# MCU.net
KiCad netlist of a schematic drawn in Altium Designer
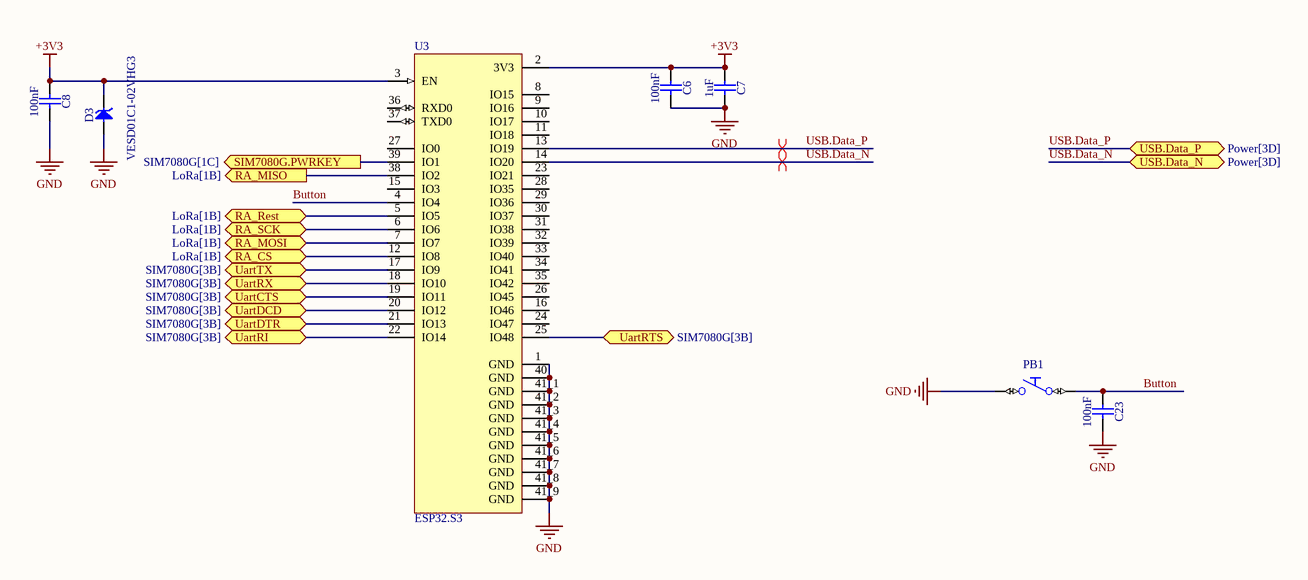
[diagram p0: MCU.SchDoc]

(export (version "E")
  (design (tool "Eeschema 10.0.6"))
  (components
    (comp (ref "C6")
      (value "100nF")
      (footprint "CAPC1608X90N")
      (description "Non-polarised capacitor")
      (fields
        (field (name "PART NUMBER") "CC0603_100NF_25V_20%_X5R_TDK_CGA3E2X5R1E104M080")
        (field (name "VOLTAGE") "25V")
        (field (name "AUTHOR") "CERN DEM BC")
      )
      (libsource (lib "Capacitors") (part "Capacitor - non polarized"))
    )
    (comp (ref "C7")
      (value "1uF")
      (footprint "CAPC1608X90N")
      (description "Non-polarised capacitor")
      (fields
        (field (name "PART NUMBER") "CC0603_1UF_10V_10%_X5R")
        (field (name "VOLTAGE") "10V")
        (field (name "AUTHOR") "CERN DEM HF")
      )
      (libsource (lib "Capacitors") (part "Capacitor - non polarized"))
    )
    (comp (ref "C8")
      (value "100nF")
      (footprint "CAPC1608X90N")
      (description "Non-polarised capacitor")
      (fields
        (field (name "PART NUMBER") "CC0603_100NF_25V_20%_X5R_TDK_CGA3E2X5R1E104M080")
        (field (name "VOLTAGE") "25V")
        (field (name "AUTHOR") "CERN DEM BC")
      )
      (libsource (lib "Capacitors") (part "Capacitor - non polarized"))
    )
    (comp (ref "C23")
      (value "100nF")
      (footprint "CAPC1608X90N")
      (description "Non-polarised capacitor")
      (fields
        (field (name "PART NUMBER") "CC0603_100NF_25V_20%_X5R_TDK_CGA3E2X5R1E104M080")
        (field (name "VOLTAGE") "25V")
        (field (name "AUTHOR") "CERN DEM BC")
      )
      (libsource (lib "Capacitors") (part "Capacitor - non polarized"))
    )
    (comp (ref "D3")
      (value "VESD01C1-02VHG3")
      (footprint "SODFL1608X70N")
      (description "Transient Voltage Suppressor Diode (Uni-Directional)")
      (fields
        (field (name "VOLTAGE") "1V")
        (field (name "POWER") "100W")
        (field (name "AUTHOR") "CERN DEM BC")
      )
      (libsource (lib "ICs And Semiconductors") (part "Diode TVS Uni-Directional"))
    )
    (comp (ref "PB1")
      (value "Push Button")
      (footprint "PB_C&K_KSS221GLFS")
      (description "Push-Button Switch SPST")
      (fields
        (field (name "PART NUMBER") "PB_C&K_KSS221GLFS")
        (field (name "MANUFACTURER") "C&K")
        (field (name "AUTHOR") "CERN DEM BC")
      )
      (libsource (lib "Eletro-mechanical") (part "PB SPST 1C-2NO"))
    )
    (comp (ref "U3")
      (value "ESP32.S3")
      (footprint "IC.ESP32.S3.WROOM.1U")
      (libsource (lib "ParsaAltiumSCHLIB") (part "IC.ESP32.S3.WROOM.1U"))
    )
  )
  (nets
    (net (code "1") (name "+3V3") (class "Default")
      (node (ref "C6") (pin "1") (pinfunction "1_1") (pintype "passive"))
      (node (ref "C7") (pin "1") (pinfunction "1_1") (pintype "passive"))
      (node (ref "C8") (pin "1") (pinfunction "1_1") (pintype "passive"))
      (node (ref "D3") (pin "1") (pinfunction "C_1") (pintype "passive"))
      (node (ref "U3") (pin "2") (pinfunction "3V3_2") (pintype "power_in"))
      (node (ref "U3") (pin "3") (pinfunction "EN_3") (pintype "input"))
    )
    (net (code "2") (name "/Button") (class "Default")
      (node (ref "C23") (pin "1") (pinfunction "1_1") (pintype "passive"))
      (node (ref "PB1") (pin "1") (pinfunction "C_1") (pintype "bidirectional"))
      (node (ref "U3") (pin "4") (pinfunction "IO4_4") (pintype "passive"))
    )
    (net (code "3") (name "/RA_CS") (class "Default")
      (node (ref "U3") (pin "12") (pinfunction "IO8_12") (pintype "passive"))
    )
    (net (code "4") (name "/RA_MISO") (class "Default")
      (node (ref "U3") (pin "38") (pinfunction "IO2_38") (pintype "passive"))
    )
    (net (code "5") (name "/RA_MOSI") (class "Default")
      (node (ref "U3") (pin "7") (pinfunction "IO7_7") (pintype "passive"))
    )
    (net (code "6") (name "/RA_Rest") (class "Default")
      (node (ref "U3") (pin "5") (pinfunction "IO5_5") (pintype "passive"))
    )
    (net (code "7") (name "/RA_SCK") (class "Default")
      (node (ref "U3") (pin "6") (pinfunction "IO6_6") (pintype "passive"))
    )
    (net (code "8") (name "/SIM7080G.PWRKEY") (class "Default")
      (node (ref "U3") (pin "39") (pinfunction "IO1_39") (pintype "passive"))
    )
    (net (code "9") (name "/USB.Data_N") (class "Default")
      (node (ref "U3") (pin "14") (pinfunction "IO20_14") (pintype "passive"))
    )
    (net (code "10") (name "/USB.Data_P") (class "Default")
      (node (ref "U3") (pin "13") (pinfunction "IO19_13") (pintype "passive"))
    )
    (net (code "11") (name "/UartCTS") (class "Default")
      (node (ref "U3") (pin "19") (pinfunction "IO11_19") (pintype "passive"))
    )
    (net (code "12") (name "/UartDCD") (class "Default")
      (node (ref "U3") (pin "20") (pinfunction "IO12_20") (pintype "passive"))
    )
    (net (code "13") (name "/UartDTR") (class "Default")
      (node (ref "U3") (pin "21") (pinfunction "IO13_21") (pintype "passive"))
    )
    (net (code "14") (name "/UartRI") (class "Default")
      (node (ref "U3") (pin "22") (pinfunction "IO14_22") (pintype "passive"))
    )
    (net (code "15") (name "/UartRTS") (class "Default")
      (node (ref "U3") (pin "25") (pinfunction "IO48_25") (pintype "passive"))
    )
    (net (code "16") (name "/UartRX") (class "Default")
      (node (ref "U3") (pin "18") (pinfunction "IO10_18") (pintype "passive"))
    )
    (net (code "17") (name "/UartTX") (class "Default")
      (node (ref "U3") (pin "17") (pinfunction "IO9_17") (pintype "passive"))
    )
    (net (code "18") (name "GND") (class "Default")
      (node (ref "C23") (pin "2") (pinfunction "2_2") (pintype "passive"))
      (node (ref "C6") (pin "2") (pinfunction "2_2") (pintype "passive"))
      (node (ref "C7") (pin "2") (pinfunction "2_2") (pintype "passive"))
      (node (ref "C8") (pin "2") (pinfunction "2_2") (pintype "passive"))
      (node (ref "D3") (pin "2") (pinfunction "A_2") (pintype "passive"))
      (node (ref "PB1") (pin "2") (pinfunction "NO_2") (pintype "bidirectional"))
      (node (ref "U3") (pin "1") (pinfunction "GND_1") (pintype "power_in"))
      (node (ref "U3") (pin "40") (pinfunction "GND_40") (pintype "power_in"))
      (node (ref "U3") (pin "41_1") (pinfunction "GND_41_1") (pintype "power_in"))
      (node (ref "U3") (pin "41_2") (pinfunction "GND_41_2") (pintype "power_in"))
      (node (ref "U3") (pin "41_3") (pinfunction "GND_41_3") (pintype "power_in"))
      (node (ref "U3") (pin "41_4") (pinfunction "GND_41_4") (pintype "power_in"))
      (node (ref "U3") (pin "41_5") (pinfunction "GND_41_5") (pintype "power_in"))
      (node (ref "U3") (pin "41_6") (pinfunction "GND_41_6") (pintype "power_in"))
      (node (ref "U3") (pin "41_7") (pinfunction "GND_41_7") (pintype "power_in"))
      (node (ref "U3") (pin "41_8") (pinfunction "GND_41_8") (pintype "power_in"))
      (node (ref "U3") (pin "41_9") (pinfunction "GND_41_9") (pintype "power_in"))
    )
    (net (code "19") (name "unconnected-(U3-IO0-Pad27)") (class "Default")
      (node (ref "U3") (pin "27") (pinfunction "IO0_27") (pintype "passive"))
    )
    (net (code "20") (name "unconnected-(U3-IO3-Pad15)") (class "Default")
      (node (ref "U3") (pin "15") (pinfunction "IO3_15") (pintype "passive"))
    )
    (net (code "21") (name "unconnected-(U3-IO15-Pad8)") (class "Default")
      (node (ref "U3") (pin "8") (pinfunction "IO15_8") (pintype "passive"))
    )
    (net (code "22") (name "unconnected-(U3-IO16-Pad9)") (class "Default")
      (node (ref "U3") (pin "9") (pinfunction "IO16_9") (pintype "passive"))
    )
    (net (code "23") (name "unconnected-(U3-IO17-Pad10)") (class "Default")
      (node (ref "U3") (pin "10") (pinfunction "IO17_10") (pintype "passive"))
    )
    (net (code "24") (name "unconnected-(U3-IO18-Pad11)") (class "Default")
      (node (ref "U3") (pin "11") (pinfunction "IO18_11") (pintype "passive"))
    )
    (net (code "25") (name "unconnected-(U3-IO21-Pad23)") (class "Default")
      (node (ref "U3") (pin "23") (pinfunction "IO21_23") (pintype "passive"))
    )
    (net (code "26") (name "unconnected-(U3-IO35-Pad28)") (class "Default")
      (node (ref "U3") (pin "28") (pinfunction "IO35_28") (pintype "passive"))
    )
    (net (code "27") (name "unconnected-(U3-IO36-Pad29)") (class "Default")
      (node (ref "U3") (pin "29") (pinfunction "IO36_29") (pintype "passive"))
    )
    (net (code "28") (name "unconnected-(U3-IO37-Pad30)") (class "Default")
      (node (ref "U3") (pin "30") (pinfunction "IO37_30") (pintype "passive"))
    )
    (net (code "29") (name "unconnected-(U3-IO38-Pad31)") (class "Default")
      (node (ref "U3") (pin "31") (pinfunction "IO38_31") (pintype "passive"))
    )
    (net (code "30") (name "unconnected-(U3-IO39-Pad32)") (class "Default")
      (node (ref "U3") (pin "32") (pinfunction "IO39_32") (pintype "passive"))
    )
    (net (code "31") (name "unconnected-(U3-IO40-Pad33)") (class "Default")
      (node (ref "U3") (pin "33") (pinfunction "IO40_33") (pintype "passive"))
    )
    (net (code "32") (name "unconnected-(U3-IO41-Pad34)") (class "Default")
      (node (ref "U3") (pin "34") (pinfunction "IO41_34") (pintype "passive"))
    )
    (net (code "33") (name "unconnected-(U3-IO42-Pad35)") (class "Default")
      (node (ref "U3") (pin "35") (pinfunction "IO42_35") (pintype "passive"))
    )
    (net (code "34") (name "unconnected-(U3-IO45-Pad26)") (class "Default")
      (node (ref "U3") (pin "26") (pinfunction "IO45_26") (pintype "passive"))
    )
    (net (code "35") (name "unconnected-(U3-IO46-Pad16)") (class "Default")
      (node (ref "U3") (pin "16") (pinfunction "IO46_16") (pintype "passive"))
    )
    (net (code "36") (name "unconnected-(U3-IO47-Pad24)") (class "Default")
      (node (ref "U3") (pin "24") (pinfunction "IO47_24") (pintype "passive"))
    )
    (net (code "37") (name "unconnected-(U3-RXD0-Pad36)") (class "Default")
      (node (ref "U3") (pin "36") (pinfunction "RXD0_36") (pintype "bidirectional"))
    )
    (net (code "38") (name "unconnected-(U3-TXD0-Pad37)") (class "Default")
      (node (ref "U3") (pin "37") (pinfunction "TXD0_37") (pintype "bidirectional"))
    )
  )
)
